# reference_0v5_ADR130.net
KiCad netlist of a schematic drawn in Altium Designer
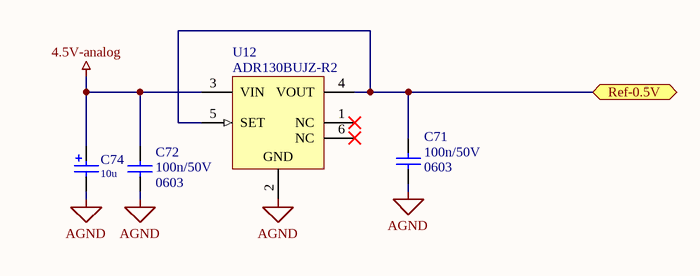
[diagram p0: reference_0v5_ADR130.SchDoc]

(export (version "E")
  (design (tool "Eeschema 10.0.6"))
  (components
    (comp (ref "C71")
      (value "100n/50V")
      (footprint "SMD_Capacitor_0603")
      (description "Ceramic Cap Kemet COTS 100n/50V X7R 0603")
      (fields
        (field (name "MANUFACTURER") "Kemet")
        (field (name "MANUFACTURERPARTNUMBER") "C0603T104K5RALTU")
        (field (name "PACKAGE") "0603")
      )
      (libsource (lib "capacitors") (part "Cer_C0603T104K5RALTU"))
    )
    (comp (ref "C72")
      (value "100n/50V")
      (footprint "SMD_Capacitor_0603")
      (description "Ceramic Cap Kemet COTS 100n/50V X7R 0603")
      (fields
        (field (name "MANUFACTURER") "Kemet")
        (field (name "MANUFACTURERPARTNUMBER") "C0603T104K5RALTU")
        (field (name "PACKAGE") "0603")
      )
      (libsource (lib "capacitors") (part "Cer_C0603T104K5RALTU"))
    )
    (comp (ref "C74")
      (value "10u")
      (footprint "Tantalum_cap_B")
      (description "Tantalum Capacitor")
      (libsource (lib "GG") (part "Cap Tantalum"))
    )
    (comp (ref "U12")
      (value "ADR130BUJZ-R2")
      (footprint "ADI-UJ-6_M")
      (fields (field (name "MANUFACTURER") "Analog Devices"))
      (libsource (lib "Analog Devices Amplifiers and Linear Voltage References") (part "ADR130BUJZ-R2"))
    )
  )
  (nets
    (net (code "1") (name "/Ref-0.5V") (class "Default")
      (node (ref "C71") (pin "1") (pinfunction "1_1") (pintype "passive"))
      (node (ref "U12") (pin "4") (pinfunction "VOUT_4") (pintype "power_in"))
      (node (ref "U12") (pin "5") (pinfunction "SET_5") (pintype "input"))
    )
    (net (code "2") (name "4.5V-analog") (class "Default")
      (node (ref "C72") (pin "1") (pinfunction "1_1") (pintype "passive"))
      (node (ref "C74") (pin "1") (pinfunction "1_1") (pintype "passive"))
      (node (ref "U12") (pin "3") (pinfunction "VIN_3") (pintype "power_in"))
    )
    (net (code "3") (name "AGND") (class "Default")
      (node (ref "C71") (pin "2") (pinfunction "2_2") (pintype "passive"))
      (node (ref "C72") (pin "2") (pinfunction "2_2") (pintype "passive"))
      (node (ref "C74") (pin "2") (pinfunction "2_2") (pintype "passive"))
      (node (ref "U12") (pin "2") (pinfunction "GND_2") (pintype "power_in"))
    )
    (net (code "4") (name "unconnected-(U12-NC-Pad1)") (class "Default")
      (node (ref "U12") (pin "1") (pinfunction "NC_1") (pintype "passive+no_connect"))
    )
    (net (code "5") (name "unconnected-(U12-NC-Pad6)") (class "Default")
      (node (ref "U12") (pin "6") (pinfunction "NC_6") (pintype "passive+no_connect"))
    )
  )
)
